# Sheet2.net
KiCad netlist of a schematic drawn in Altium Designer
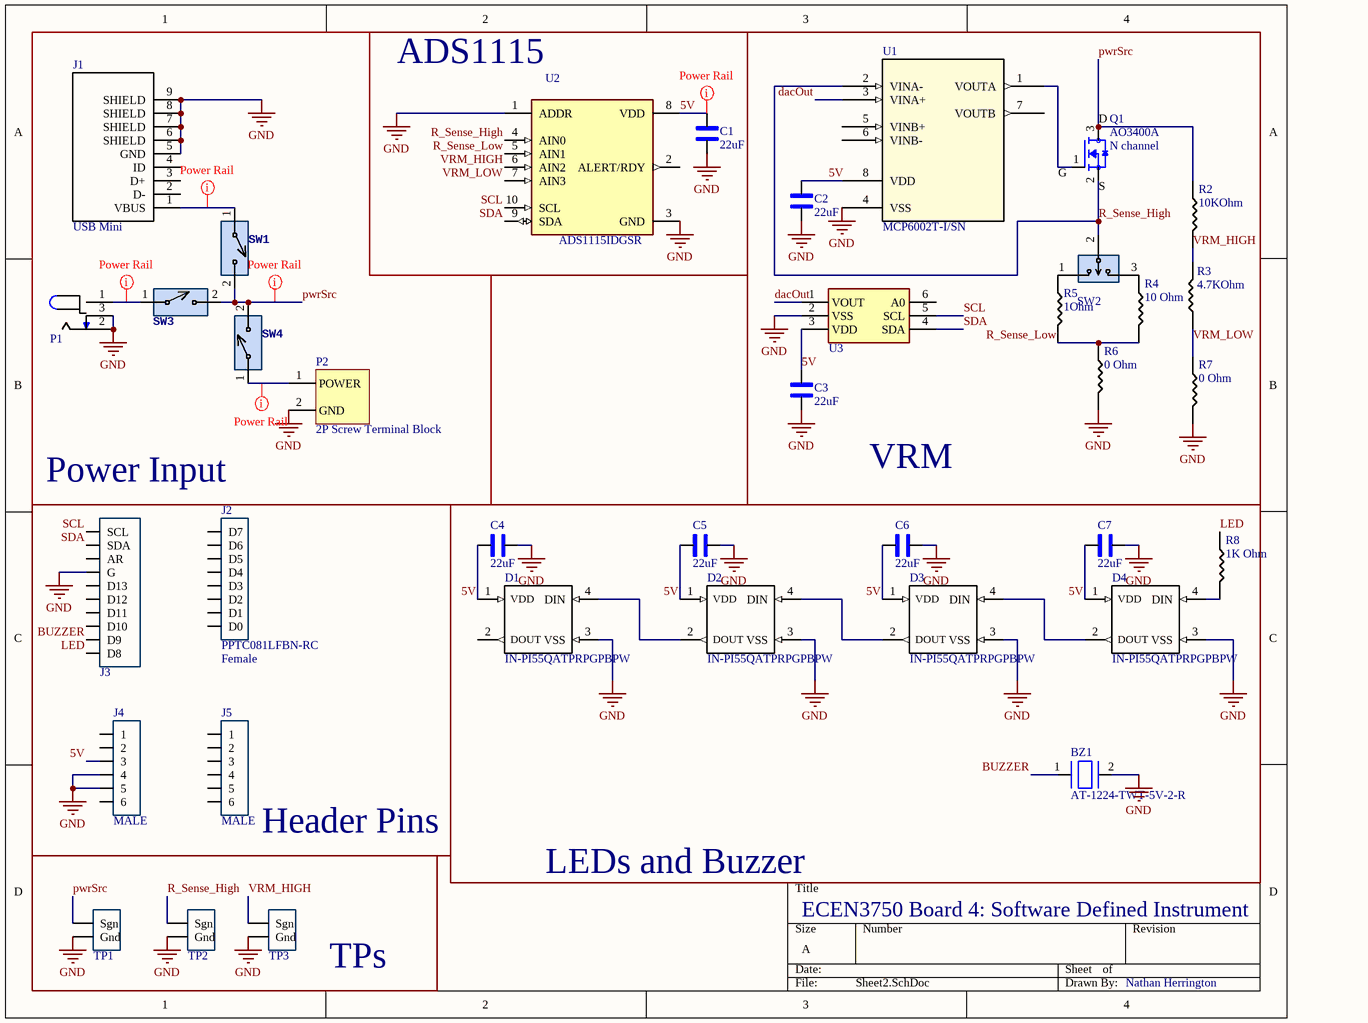
[diagram p0: Sheet2.SchDoc]

(export (version "E")
  (design (tool "Eeschema 10.0.6"))
  (components
    (comp (ref "BZ1")
      (value "AT-1224-TWT-5V-2-R")
      (footprint "BUZZER- TH")
      (fields (field (name "MFR PART #") "AT-1224-TWT-5V-2-R"))
      (libsource (lib "ECEN5730Lib_2023_05_DS") (part "BUZZER_1"))
    )
    (comp (ref "C1")
      (value "22uF")
      (footprint "1206_Passive_Capacitor")
      (description "22uF ±10% 25V X5R 1206 Multilayer Ceramic Capacitors MLCC - SMD/SMT RoHS")
      (fields (field (name "MFR PART #") "CL31A226KAHNNNE") (field (name "LCSC PART#") "C12891"))
      (libsource (lib "ECEN5730Lib_2023_05_DS") (part "C_22uF_1206"))
    )
    (comp (ref "C2")
      (value "22uF")
      (footprint "1206_Passive_Capacitor")
      (description "22uF ±10% 25V X5R 1206 Multilayer Ceramic Capacitors MLCC - SMD/SMT RoHS")
      (fields (field (name "MFR PART #") "CL31A226KAHNNNE") (field (name "LCSC PART#") "C12891"))
      (libsource (lib "ECEN5730Lib_2023_05_DS") (part "C_22uF_1206"))
    )
    (comp (ref "C3")
      (value "22uF")
      (footprint "1206_Passive_Capacitor")
      (description "22uF ±10% 25V X5R 1206 Multilayer Ceramic Capacitors MLCC - SMD/SMT RoHS")
      (fields (field (name "MFR PART #") "CL31A226KAHNNNE") (field (name "LCSC PART#") "C12891"))
      (libsource (lib "ECEN5730Lib_2023_05_DS") (part "C_22uF_1206"))
    )
    (comp (ref "C4")
      (value "22uF")
      (footprint "1206_Passive_Capacitor")
      (description "22uF ±10% 25V X5R 1206 Multilayer Ceramic Capacitors MLCC - SMD/SMT RoHS")
      (fields (field (name "MFR PART #") "CL31A226KAHNNNE") (field (name "LCSC PART#") "C12891"))
      (libsource (lib "ECEN5730Lib_2023_05_DS") (part "C_22uF_1206"))
    )
    (comp (ref "C5")
      (value "22uF")
      (footprint "1206_Passive_Capacitor")
      (description "22uF ±10% 25V X5R 1206 Multilayer Ceramic Capacitors MLCC - SMD/SMT RoHS")
      (fields (field (name "MFR PART #") "CL31A226KAHNNNE") (field (name "LCSC PART#") "C12891"))
      (libsource (lib "ECEN5730Lib_2023_05_DS") (part "C_22uF_1206"))
    )
    (comp (ref "C6")
      (value "22uF")
      (footprint "1206_Passive_Capacitor")
      (description "22uF ±10% 25V X5R 1206 Multilayer Ceramic Capacitors MLCC - SMD/SMT RoHS")
      (fields (field (name "MFR PART #") "CL31A226KAHNNNE") (field (name "LCSC PART#") "C12891"))
      (libsource (lib "ECEN5730Lib_2023_05_DS") (part "C_22uF_1206"))
    )
    (comp (ref "C7")
      (value "22uF")
      (footprint "1206_Passive_Capacitor")
      (description "22uF ±10% 25V X5R 1206 Multilayer Ceramic Capacitors MLCC - SMD/SMT RoHS")
      (fields (field (name "MFR PART #") "CL31A226KAHNNNE") (field (name "LCSC PART#") "C12891"))
      (libsource (lib "ECEN5730Lib_2023_05_DS") (part "C_22uF_1206"))
    )
    (comp (ref "D1")
      (value "IN-PI55QATPRPGPBPW")
      (footprint "SERIAL_LED - duplicate")
      (fields
        (field (name "LCSC PART#") "C2843785")
        (field (name "MFR PART #") "XL-5050RGBC-WS2812B")
        (field (name "MANUFACTURER") "XINGLIGHT")
      )
      (libsource (lib "ECEN5730Lib_2023_05_DS") (part "LED_Smart"))
    )
    (comp (ref "D2")
      (value "IN-PI55QATPRPGPBPW")
      (footprint "SERIAL_LED - duplicate")
      (fields
        (field (name "LCSC PART#") "C2843785")
        (field (name "MFR PART #") "XL-5050RGBC-WS2812B")
        (field (name "MANUFACTURER") "XINGLIGHT")
      )
      (libsource (lib "ECEN5730Lib_2023_05_DS") (part "LED_Smart"))
    )
    (comp (ref "D3")
      (value "IN-PI55QATPRPGPBPW")
      (footprint "SERIAL_LED - duplicate")
      (fields
        (field (name "LCSC PART#") "C2843785")
        (field (name "MFR PART #") "XL-5050RGBC-WS2812B")
        (field (name "MANUFACTURER") "XINGLIGHT")
      )
      (libsource (lib "ECEN5730Lib_2023_05_DS") (part "LED_Smart"))
    )
    (comp (ref "D4")
      (value "IN-PI55QATPRPGPBPW")
      (footprint "SERIAL_LED - duplicate")
      (fields
        (field (name "LCSC PART#") "C2843785")
        (field (name "MFR PART #") "XL-5050RGBC-WS2812B")
        (field (name "MANUFACTURER") "XINGLIGHT")
      )
      (libsource (lib "ECEN5730Lib_2023_05_DS") (part "LED_Smart"))
    )
    (comp (ref "J1")
      (value "USB Mini")
      (footprint "USB_MINI_B")
      (description "Through Hole USB Connectors RoHS")
      (fields (field (name "LCSC PART#") "C46398") (field (name "MFR PART #") "920-462A2021D10102"))
      (libsource (lib "ECEN5730Lib_2023_05_DS") (part "J_USB_B_Mini"))
    )
    (comp (ref "J2")
      (value "PPTC081LFBN-RC")
      (footprint "8_PIN_ARD-DIG_100MIL")
      (description "8 Position Header Connector 0.100\" (2.54mm) Through Hole Tin")
      (fields (field (name "LCSC PART#") "C27438") (field (name "ALTIUM_VALUE") "Female"))
      (libsource (lib "ECEN5730Lib_2023_05_DS") (part "JF_8_PIN_FEMA_ARD-Dig"))
    )
    (comp (ref "J3")
      (value "PPTC101LFBN-RC")
      (footprint "10_PIN_ARDUINO_100MIL")
      (description "10 Position Header Connector 0.100\" (2.54mm) Through Hole Tin")
      (fields (field (name "LCSC PART#") "C225507"))
      (libsource (lib "ECEN5730Lib_2023_05_DS") (part "JF_10_PIN_FEMA_ARDUINO"))
    )
    (comp (ref "J4")
      (value "MALE")
      (footprint "6_PIN_100MIL-Male")
      (description "Male header- 6 pin 1 row- through Hole")
      (fields (field (name "LCSC PART#") "C37208"))
      (libsource (lib "ECEN5730Lib_2023_05_DS") (part "JM_6_PIN_MALE"))
    )
    (comp (ref "J5")
      (value "MALE")
      (footprint "6_PIN_100MIL-Male")
      (description "Male header- 6 pin 1 row- through Hole")
      (fields (field (name "LCSC PART#") "C37208"))
      (libsource (lib "ECEN5730Lib_2023_05_DS") (part "JM_6_PIN_MALE"))
    )
    (comp (ref "P1")
      (value "Power Jack")
      (footprint "Power_Jack")
      (description "Power Barrel Connector Jack 2.10mm ID (0.083\"), 5.50mm OD (0.217\") Through Hole, Right Angle")
      (fields (field (name "MFR PART #") "PJ-102A") (field (name "LCSC PART#") "C136744"))
      (libsource (lib "ECEN5730Lib_2023_05_DS") (part "P_Power Jack"))
    )
    (comp (ref "P2")
      (value "2P Screw Terminal Block")
      (footprint "P_Terminal block 3.5mm-pitch")
      (description "Green Straight pin 3.5mm  pitch; P=3.5mm  Screw terminal ROHS")
      (fields (field (name "MFR PART #") "KF350-3.5-2P") (field (name "MANUFACTURER") "Cixi Kefa Elec"))
      (libsource (lib "ECEN5730Lib_2023_05_DS") (part "P_Terminal block"))
    )
    (comp (ref "Q1")
      (value "AO3400A")
      (footprint "N-MOSFET")
      (description "MOSFET N Trench 30V 5.7A 1.5V @ 250uA 26.5 m? @ 5.7A,10V SOT-23-3L RoHS")
      (fields (field (name "LCSC PART#") "C20917") (field (name "ALTIUM_VALUE") "N channel"))
      (libsource (lib "ECEN5730Lib_2023_05_DS") (part "Q_Nch_MOSFET"))
    )
    (comp (ref "R2")
      (value "10KOhm")
      (footprint "1206_Passive_Resitor")
      (description "10 kOhms ±5% 0.25W, 1/4W Chip Resistor 1206 (3216 Metric) Automotive AEC-Q200 Thick Film")
      (fields (field (name "MFR PART #") "RMCF1206FT10K0") (field (name "LCSC PART#") "C17902"))
      (libsource (lib "ECEN5730Lib_2023_05_DS") (part "R_10KOhm_1206"))
    )
    (comp (ref "R3")
      (value "4.7KOhm")
      (footprint "1206_Passive_Resitor")
      (description "4.7kΩ ±1% 0.25W ±100ppm/℃ 1206 Chip Resistor - Surface Mount RoHS")
      (fields (field (name "LCSC PART#") "C17936") (field (name "MFR PART #") "1206W4F4701T5E"))
      (libsource (lib "ECEN5730Lib_2023_05_DS") (part "R_4.7k_1206"))
    )
    (comp (ref "R4")
      (value "10 Ohm")
      (footprint "1206_Passive_Resitor")
      (description "CHIP RESISTOR - SURFACE MOUNT 0.1OHMS ±1% 1/4W 1206 ROHS")
      (fields (field (name "MFR PART #") "1206W4F100JT5E") (field (name "LCSC PART#") "C17903"))
      (libsource (lib "ECEN5730Lib_2023_05_DS") (part "R_10Ohm_1206"))
    )
    (comp (ref "R5")
      (value "1Ohm")
      (footprint "1206_Passive_Resitor")
      (description "1Ω ±5% 0.25W ±400ppm/℃ 1206 Chip Resistor - Surface Mount RoHS")
      (fields (field (name "LCSC PART#") "C1409") (field (name "MFR PART #") "1206W4J010JT5E"))
      (libsource (lib "ECEN5730Lib_2023_05_DS") (part "R_1Ohm_1206"))
    )
    (comp (ref "R6")
      (value "0 Ohm")
      (footprint "1206_Passive_Resitor")
      (description "CHIP RESISTOR - SURFACE MOUNT 0OHMS ±1% 1/4W 1206 ROHS")
      (fields (field (name "MFR PART #") "1206W4F0000T5E") (field (name "LCSC PART#") "C17888"))
      (libsource (lib "ECEN5730Lib_2023_05_DS") (part "R_0Ohm_1206"))
    )
    (comp (ref "R7")
      (value "0 Ohm")
      (footprint "1206_Passive_Resitor")
      (description "CHIP RESISTOR - SURFACE MOUNT 0OHMS ±1% 1/4W 1206 ROHS")
      (fields (field (name "MFR PART #") "1206W4F0000T5E") (field (name "LCSC PART#") "C17888"))
      (libsource (lib "ECEN5730Lib_2023_05_DS") (part "R_0Ohm_1206"))
    )
    (comp (ref "R8")
      (value "1K Ohm")
      (footprint "1206_Passive_Resitor")
      (description "CHIP RESISTOR - SURFACE MOUNT 1KOHMS ±1% 1/4W 1206 ROHS")
      (fields (field (name "MFR PART #") "RNCP1206FTD1K00CT") (field (name "LCSC PART#") "C4410"))
      (libsource (lib "ECEN5730Lib_2023_05_DS") (part "R_1K_1206"))
    )
    (comp (ref "SW1")
      (value "SW_2Pin_100mil_Switch")
      (footprint "2Pin-Header-Conn")
      (description "2Pin Header")
      (fields (field (name "LCSC PART#") "C124375"))
      (libsource (lib "") (part "SW_2Pin_100mil_Switch_2"))
    )
    (comp (ref "SW2")
      (value "PREC003SAAN-RC")
      (footprint "3_PIN_100mil")
      (description "Connector Header Through Hole 3 position 0.100\" (2.54mm)")
      (fields (field (name "LCSC PART#") "C49257"))
      (libsource (lib "ECEN5730Lib_2023_05_DS") (part "SW_3Pin_100mil_Switch"))
    )
    (comp (ref "SW3")
      (value "SW_2Pin_100mil_Switch")
      (footprint "2Pin-Header-Conn")
      (description "2Pin Header")
      (fields (field (name "LCSC PART#") "C124375"))
      (libsource (lib "") (part "SW_2Pin_100mil_Switch_1"))
    )
    (comp (ref "SW4")
      (value "SW_2Pin_100mil_Switch")
      (footprint "2Pin-Header-Conn")
      (description "2Pin Header")
      (fields (field (name "LCSC PART#") "C124375"))
      (libsource (lib "ECEN5730Lib_2023_05_DS") (part "SW_2Pin_100mil_Switch"))
    )
    (comp (ref "TP1")
      (value "10x Probe TP")
      (footprint "TP10x_Probe")
      (description "Test Point 300 mil centers")
      (libsource (lib "ECEN5730Lib_2023_05_DS") (part "TP_10x_Probe"))
    )
    (comp (ref "TP2")
      (value "10x Probe TP")
      (footprint "TP10x_Probe")
      (description "Test Point 300 mil centers")
      (libsource (lib "ECEN5730Lib_2023_05_DS") (part "TP_10x_Probe"))
    )
    (comp (ref "TP3")
      (value "10x Probe TP")
      (footprint "TP10x_Probe")
      (description "Test Point 300 mil centers")
      (libsource (lib "ECEN5730Lib_2023_05_DS") (part "TP_10x_Probe"))
    )
    (comp (ref "U1")
      (value "MCP6002T-I/SN")
      (footprint "SOIC127P600X175-8N")
      (description "0.6 V/us 2 1MHz 1.8V ~ 6V 100μA General Purpose SOIC-8_150mil  Operational Amplifier ROHS")
      (fields (field (name "MFR") "Microchip") (field (name "LCSC PART#") "C7377"))
      (libsource (lib "ECEN5730Lib_2023_05_DS") (part "U_MCP6002T-I/SN"))
    )
    (comp (ref "U2")
      (value "ADS1115IDGSR")
      (footprint "ADC_ADS1115IDGSR")
      (description "16-Bit ADC with Integrated MUX, PGA, Comparator, Oscillator, and Reference 10-VSSOP -40 to 125")
      (fields (field (name "LCSC PART#") "C37593"))
      (libsource (lib "ECEN5730Lib_2023_05_DS") (part "U_ADC_ADS1115IDGSR"))
    )
    (comp (ref "U3")
      (value "DAC IC")
      (footprint "MCP4725")
      (description "IC DAC 12BIT V-OUT SOT23-6")
      (fields (field (name "LCSC PART#") "C144198") (field (name "MFR PART #") "MCP4725A0T-E/CH"))
      (libsource (lib "ECEN5730Lib_2023_05_DS") (part "U_MCP4725A0T-E/CH"))
    )
  )
  (nets
    (net (code "1") (name "/5V") (class "Default")
      (node (ref "C1") (pin "1") (pinfunction "1_1") (pintype "passive"))
      (node (ref "C2") (pin "1") (pinfunction "1_1") (pintype "passive"))
      (node (ref "C3") (pin "1") (pinfunction "1_1") (pintype "passive"))
      (node (ref "C4") (pin "2") (pinfunction "2_2") (pintype "passive"))
      (node (ref "C5") (pin "2") (pinfunction "2_2") (pintype "passive"))
      (node (ref "C6") (pin "2") (pinfunction "2_2") (pintype "passive"))
      (node (ref "C7") (pin "2") (pinfunction "2_2") (pintype "passive"))
      (node (ref "D1") (pin "1") (pinfunction "VDD_1") (pintype "input"))
      (node (ref "D2") (pin "1") (pinfunction "VDD_1") (pintype "input"))
      (node (ref "D3") (pin "1") (pinfunction "VDD_1") (pintype "input"))
      (node (ref "D4") (pin "1") (pinfunction "VDD_1") (pintype "input"))
      (node (ref "J4") (pin "3") (pinfunction "3_3") (pintype "passive"))
      (node (ref "U1") (pin "8") (pinfunction "VDD_8") (pintype "passive"))
      (node (ref "U2") (pin "8") (pinfunction "VDD_8") (pintype "power_in"))
      (node (ref "U3") (pin "3") (pinfunction "VDD_3") (pintype "passive"))
    )
    (net (code "2") (name "/BUZZER") (class "Default")
      (node (ref "BZ1") (pin "1") (pinfunction "BZ1_1") (pintype "passive"))
      (node (ref "J3") (pin "9") (pinfunction "D9_9") (pintype "passive"))
    )
    (net (code "3") (name "/LED") (class "Default")
      (node (ref "J3") (pin "10") (pinfunction "D8_10") (pintype "passive"))
      (node (ref "R8") (pin "1") (pinfunction "1_1") (pintype "passive"))
    )
    (net (code "4") (name "/R_Sense_High") (class "Default")
      (node (ref "Q1") (pin "2") (pinfunction "S_2") (pintype "passive"))
      (node (ref "SW2") (pin "2") (pinfunction "2_2") (pintype "passive"))
      (node (ref "TP2") (pin "1") (pinfunction "Sgn_1") (pintype "passive"))
      (node (ref "U1") (pin "2") (pinfunction "VINA-_2") (pintype "input"))
      (node (ref "U2") (pin "4") (pinfunction "AIN0_4") (pintype "input"))
    )
    (net (code "5") (name "/R_Sense_Low") (class "Default")
      (node (ref "R4") (pin "2") (pinfunction "2_2") (pintype "passive"))
      (node (ref "R5") (pin "2") (pinfunction "2_2") (pintype "passive"))
      (node (ref "R6") (pin "1") (pinfunction "1_1") (pintype "passive"))
      (node (ref "U2") (pin "5") (pinfunction "AIN1_5") (pintype "input"))
    )
    (net (code "6") (name "/SCL") (class "Default")
      (node (ref "J3") (pin "1") (pinfunction "SCL_1") (pintype "passive"))
      (node (ref "U2") (pin "10") (pinfunction "SCL_10") (pintype "input"))
      (node (ref "U3") (pin "5") (pinfunction "SCL_5") (pintype "passive"))
    )
    (net (code "7") (name "/SDA") (class "Default")
      (node (ref "J3") (pin "2") (pinfunction "SDA_2") (pintype "passive"))
      (node (ref "U2") (pin "9") (pinfunction "SDA_9") (pintype "bidirectional"))
      (node (ref "U3") (pin "4") (pinfunction "SDA_4") (pintype "passive"))
    )
    (net (code "8") (name "/VRM_HIGH") (class "Default")
      (node (ref "R2") (pin "2") (pinfunction "2_2") (pintype "passive"))
      (node (ref "R3") (pin "2") (pinfunction "2_2") (pintype "passive"))
      (node (ref "TP3") (pin "1") (pinfunction "Sgn_1") (pintype "passive"))
      (node (ref "U2") (pin "6") (pinfunction "AIN2_6") (pintype "input"))
    )
    (net (code "9") (name "/VRM_LOW") (class "Default")
      (node (ref "R3") (pin "1") (pinfunction "1_1") (pintype "passive"))
      (node (ref "R7") (pin "1") (pinfunction "1_1") (pintype "passive"))
      (node (ref "U2") (pin "7") (pinfunction "AIN3_7") (pintype "input"))
    )
    (net (code "10") (name "/dacOut") (class "Default")
      (node (ref "U1") (pin "3") (pinfunction "VINA+_3") (pintype "input"))
      (node (ref "U3") (pin "1") (pinfunction "VOUT_1") (pintype "passive"))
    )
    (net (code "11") (name "/pwrSrc") (class "Default")
      (node (ref "Q1") (pin "3") (pinfunction "D_3") (pintype "passive"))
      (node (ref "R2") (pin "1") (pinfunction "1_1") (pintype "passive"))
      (node (ref "SW1") (pin "2") (pinfunction "2_2") (pintype "passive"))
      (node (ref "SW3") (pin "2") (pinfunction "2_2") (pintype "passive"))
      (node (ref "SW4") (pin "2") (pinfunction "2_2") (pintype "passive"))
      (node (ref "TP1") (pin "1") (pinfunction "Sgn_1") (pintype "passive"))
    )
    (net (code "12") (name "GND") (class "Default")
      (node (ref "BZ1") (pin "2") (pinfunction "BZ2_2") (pintype "passive"))
      (node (ref "C1") (pin "2") (pinfunction "2_2") (pintype "passive"))
      (node (ref "C2") (pin "2") (pinfunction "2_2") (pintype "passive"))
      (node (ref "C3") (pin "2") (pinfunction "2_2") (pintype "passive"))
      (node (ref "C4") (pin "1") (pinfunction "1_1") (pintype "passive"))
      (node (ref "C5") (pin "1") (pinfunction "1_1") (pintype "passive"))
      (node (ref "C6") (pin "1") (pinfunction "1_1") (pintype "passive"))
      (node (ref "C7") (pin "1") (pinfunction "1_1") (pintype "passive"))
      (node (ref "D1") (pin "3") (pinfunction "VSS_3") (pintype "input"))
      (node (ref "D2") (pin "3") (pinfunction "VSS_3") (pintype "input"))
      (node (ref "D3") (pin "3") (pinfunction "VSS_3") (pintype "input"))
      (node (ref "D4") (pin "3") (pinfunction "VSS_3") (pintype "input"))
      (node (ref "J1") (pin "5") (pinfunction "GND_5") (pintype "passive"))
      (node (ref "J1") (pin "6") (pinfunction "SHIELD_6") (pintype "passive"))
      (node (ref "J1") (pin "7") (pinfunction "SHIELD_7") (pintype "passive"))
      (node (ref "J1") (pin "8") (pinfunction "SHIELD_8") (pintype "passive"))
      (node (ref "J1") (pin "9") (pinfunction "SHIELD_9") (pintype "passive"))
      (node (ref "J3") (pin "4") (pinfunction "G_4") (pintype "passive"))
      (node (ref "J4") (pin "4") (pinfunction "4_4") (pintype "passive"))
      (node (ref "J4") (pin "5") (pinfunction "5_5") (pintype "passive"))
      (node (ref "P1") (pin "2") (pinfunction "2_2") (pintype "power_in"))
      (node (ref "P1") (pin "3") (pinfunction "3_3") (pintype "power_in"))
      (node (ref "P2") (pin "2") (pinfunction "GND_2") (pintype "passive"))
      (node (ref "R6") (pin "2") (pinfunction "2_2") (pintype "passive"))
      (node (ref "R7") (pin "2") (pinfunction "2_2") (pintype "passive"))
      (node (ref "TP1") (pin "2") (pinfunction "Gnd_2") (pintype "passive"))
      (node (ref "TP2") (pin "2") (pinfunction "Gnd_2") (pintype "passive"))
      (node (ref "TP3") (pin "2") (pinfunction "Gnd_2") (pintype "passive"))
      (node (ref "U1") (pin "4") (pinfunction "VSS_4") (pintype "passive"))
      (node (ref "U2") (pin "1") (pinfunction "ADDR_1") (pintype "passive"))
      (node (ref "U2") (pin "3") (pinfunction "GND_3") (pintype "power_in"))
      (node (ref "U3") (pin "2") (pinfunction "VSS_2") (pintype "passive"))
    )
    (net (code "13") (name "Net-(D1-DIN)") (class "Default")
      (node (ref "D1") (pin "4") (pinfunction "DIN_4") (pintype "input"))
      (node (ref "D2") (pin "2") (pinfunction "DOUT_2") (pintype "output"))
    )
    (net (code "14") (name "Net-(D2-DIN)") (class "Default")
      (node (ref "D2") (pin "4") (pinfunction "DIN_4") (pintype "input"))
      (node (ref "D3") (pin "2") (pinfunction "DOUT_2") (pintype "output"))
    )
    (net (code "15") (name "Net-(D3-DIN)") (class "Default")
      (node (ref "D3") (pin "4") (pinfunction "DIN_4") (pintype "input"))
      (node (ref "D4") (pin "2") (pinfunction "DOUT_2") (pintype "output"))
    )
    (net (code "16") (name "Net-(D4-DIN)") (class "Default")
      (node (ref "D4") (pin "4") (pinfunction "DIN_4") (pintype "input"))
      (node (ref "R8") (pin "2") (pinfunction "2_2") (pintype "passive"))
    )
    (net (code "17") (name "Net-(J1-VBUS)") (class "Default")
      (node (ref "J1") (pin "1") (pinfunction "VBUS_1") (pintype "passive"))
      (node (ref "SW1") (pin "1") (pinfunction "1_1") (pintype "passive"))
    )
    (net (code "18") (name "Net-(P1-Pad1)") (class "Default")
      (node (ref "P1") (pin "1") (pinfunction "1_1") (pintype "power_in"))
      (node (ref "SW3") (pin "1") (pinfunction "1_1") (pintype "passive"))
    )
    (net (code "19") (name "Net-(P2-POWER)") (class "Default")
      (node (ref "P2") (pin "1") (pinfunction "POWER_1") (pintype "passive"))
      (node (ref "SW4") (pin "1") (pinfunction "1_1") (pintype "passive"))
    )
    (net (code "20") (name "Net-(Q1-G)") (class "Default")
      (node (ref "Q1") (pin "1") (pinfunction "G_1") (pintype "passive"))
      (node (ref "U1") (pin "1") (pinfunction "VOUTA_1") (pintype "output"))
    )
    (net (code "21") (name "Net-(R4-Pad1)") (class "Default")
      (node (ref "R4") (pin "1") (pinfunction "1_1") (pintype "passive"))
      (node (ref "SW2") (pin "3") (pinfunction "3_3") (pintype "passive"))
    )
    (net (code "22") (name "Net-(R5-Pad1)") (class "Default")
      (node (ref "R5") (pin "1") (pinfunction "1_1") (pintype "passive"))
      (node (ref "SW2") (pin "1") (pinfunction "1_1") (pintype "passive"))
    )
    (net (code "23") (name "unconnected-(D1-DOUT-Pad2)") (class "Default")
      (node (ref "D1") (pin "2") (pinfunction "DOUT_2") (pintype "output"))
    )
    (net (code "24") (name "unconnected-(J1-D+-Pad3)") (class "Default")
      (node (ref "J1") (pin "3") (pinfunction "D+_3") (pintype "passive"))
    )
    (net (code "25") (name "unconnected-(J1-D--Pad2)") (class "Default")
      (node (ref "J1") (pin "2") (pinfunction "D-_2") (pintype "passive"))
    )
    (net (code "26") (name "unconnected-(J1-ID-Pad4)") (class "Default")
      (node (ref "J1") (pin "4") (pinfunction "ID_4") (pintype "passive"))
    )
    (net (code "27") (name "unconnected-(J2-D0-Pad8)") (class "Default")
      (node (ref "J2") (pin "8") (pinfunction "D0_8") (pintype "passive"))
    )
    (net (code "28") (name "unconnected-(J2-D1-Pad7)") (class "Default")
      (node (ref "J2") (pin "7") (pinfunction "D1_7") (pintype "passive"))
    )
    (net (code "29") (name "unconnected-(J2-D2-Pad6)") (class "Default")
      (node (ref "J2") (pin "6") (pinfunction "D2_6") (pintype "passive"))
    )
    (net (code "30") (name "unconnected-(J2-D3-Pad5)") (class "Default")
      (node (ref "J2") (pin "5") (pinfunction "D3_5") (pintype "passive"))
    )
    (net (code "31") (name "unconnected-(J2-D4-Pad4)") (class "Default")
      (node (ref "J2") (pin "4") (pinfunction "D4_4") (pintype "passive"))
    )
    (net (code "32") (name "unconnected-(J2-D5-Pad3)") (class "Default")
      (node (ref "J2") (pin "3") (pinfunction "D5_3") (pintype "passive"))
    )
    (net (code "33") (name "unconnected-(J2-D6-Pad2)") (class "Default")
      (node (ref "J2") (pin "2") (pinfunction "D6_2") (pintype "passive"))
    )
    (net (code "34") (name "unconnected-(J2-D7-Pad1)") (class "Default")
      (node (ref "J2") (pin "1") (pinfunction "D7_1") (pintype "passive"))
    )
    (net (code "35") (name "unconnected-(J3-AR-Pad3)") (class "Default")
      (node (ref "J3") (pin "3") (pinfunction "AR_3") (pintype "passive"))
    )
    (net (code "36") (name "unconnected-(J3-D10-Pad8)") (class "Default")
      (node (ref "J3") (pin "8") (pinfunction "D10_8") (pintype "passive"))
    )
    (net (code "37") (name "unconnected-(J3-D11-Pad7)") (class "Default")
      (node (ref "J3") (pin "7") (pinfunction "D11_7") (pintype "passive"))
    )
    (net (code "38") (name "unconnected-(J3-D12-Pad6)") (class "Default")
      (node (ref "J3") (pin "6") (pinfunction "D12_6") (pintype "passive"))
    )
    (net (code "39") (name "unconnected-(J3-D13-Pad5)") (class "Default")
      (node (ref "J3") (pin "5") (pinfunction "D13_5") (pintype "passive"))
    )
    (net (code "40") (name "unconnected-(J4-Pad1)") (class "Default")
      (node (ref "J4") (pin "1") (pinfunction "1_1") (pintype "passive"))
    )
    (net (code "41") (name "unconnected-(J4-Pad2)") (class "Default")
      (node (ref "J4") (pin "2") (pinfunction "2_2") (pintype "passive"))
    )
    (net (code "42") (name "unconnected-(J4-Pad6)") (class "Default")
      (node (ref "J4") (pin "6") (pinfunction "6_6") (pintype "passive"))
    )
    (net (code "43") (name "unconnected-(J5-Pad1)") (class "Default")
      (node (ref "J5") (pin "1") (pinfunction "1_1") (pintype "passive"))
    )
    (net (code "44") (name "unconnected-(J5-Pad2)") (class "Default")
      (node (ref "J5") (pin "2") (pinfunction "2_2") (pintype "passive"))
    )
    (net (code "45") (name "unconnected-(J5-Pad3)") (class "Default")
      (node (ref "J5") (pin "3") (pinfunction "3_3") (pintype "passive"))
    )
    (net (code "46") (name "unconnected-(J5-Pad4)") (class "Default")
      (node (ref "J5") (pin "4") (pinfunction "4_4") (pintype "passive"))
    )
    (net (code "47") (name "unconnected-(J5-Pad5)") (class "Default")
      (node (ref "J5") (pin "5") (pinfunction "5_5") (pintype "passive"))
    )
    (net (code "48") (name "unconnected-(J5-Pad6)") (class "Default")
      (node (ref "J5") (pin "6") (pinfunction "6_6") (pintype "passive"))
    )
    (net (code "49") (name "unconnected-(U1-VINB+-Pad5)") (class "Default")
      (node (ref "U1") (pin "5") (pinfunction "VINB+_5") (pintype "input"))
    )
    (net (code "50") (name "unconnected-(U1-VINB--Pad6)") (class "Default")
      (node (ref "U1") (pin "6") (pinfunction "VINB-_6") (pintype "input"))
    )
    (net (code "51") (name "unconnected-(U1-VOUTB-Pad7)") (class "Default")
      (node (ref "U1") (pin "7") (pinfunction "VOUTB_7") (pintype "output"))
    )
    (net (code "52") (name "unconnected-(U2-ALERT{slash}RDY-Pad2)") (class "Default")
      (node (ref "U2") (pin "2") (pinfunction "ALERT/RDY_2") (pintype "output"))
    )
    (net (code "53") (name "unconnected-(U3-A0-Pad6)") (class "Default")
      (node (ref "U3") (pin "6") (pinfunction "A0_6") (pintype "passive"))
    )
  )
)
